# SmartClock.net
KiCad netlist of a schematic drawn in EAGLE
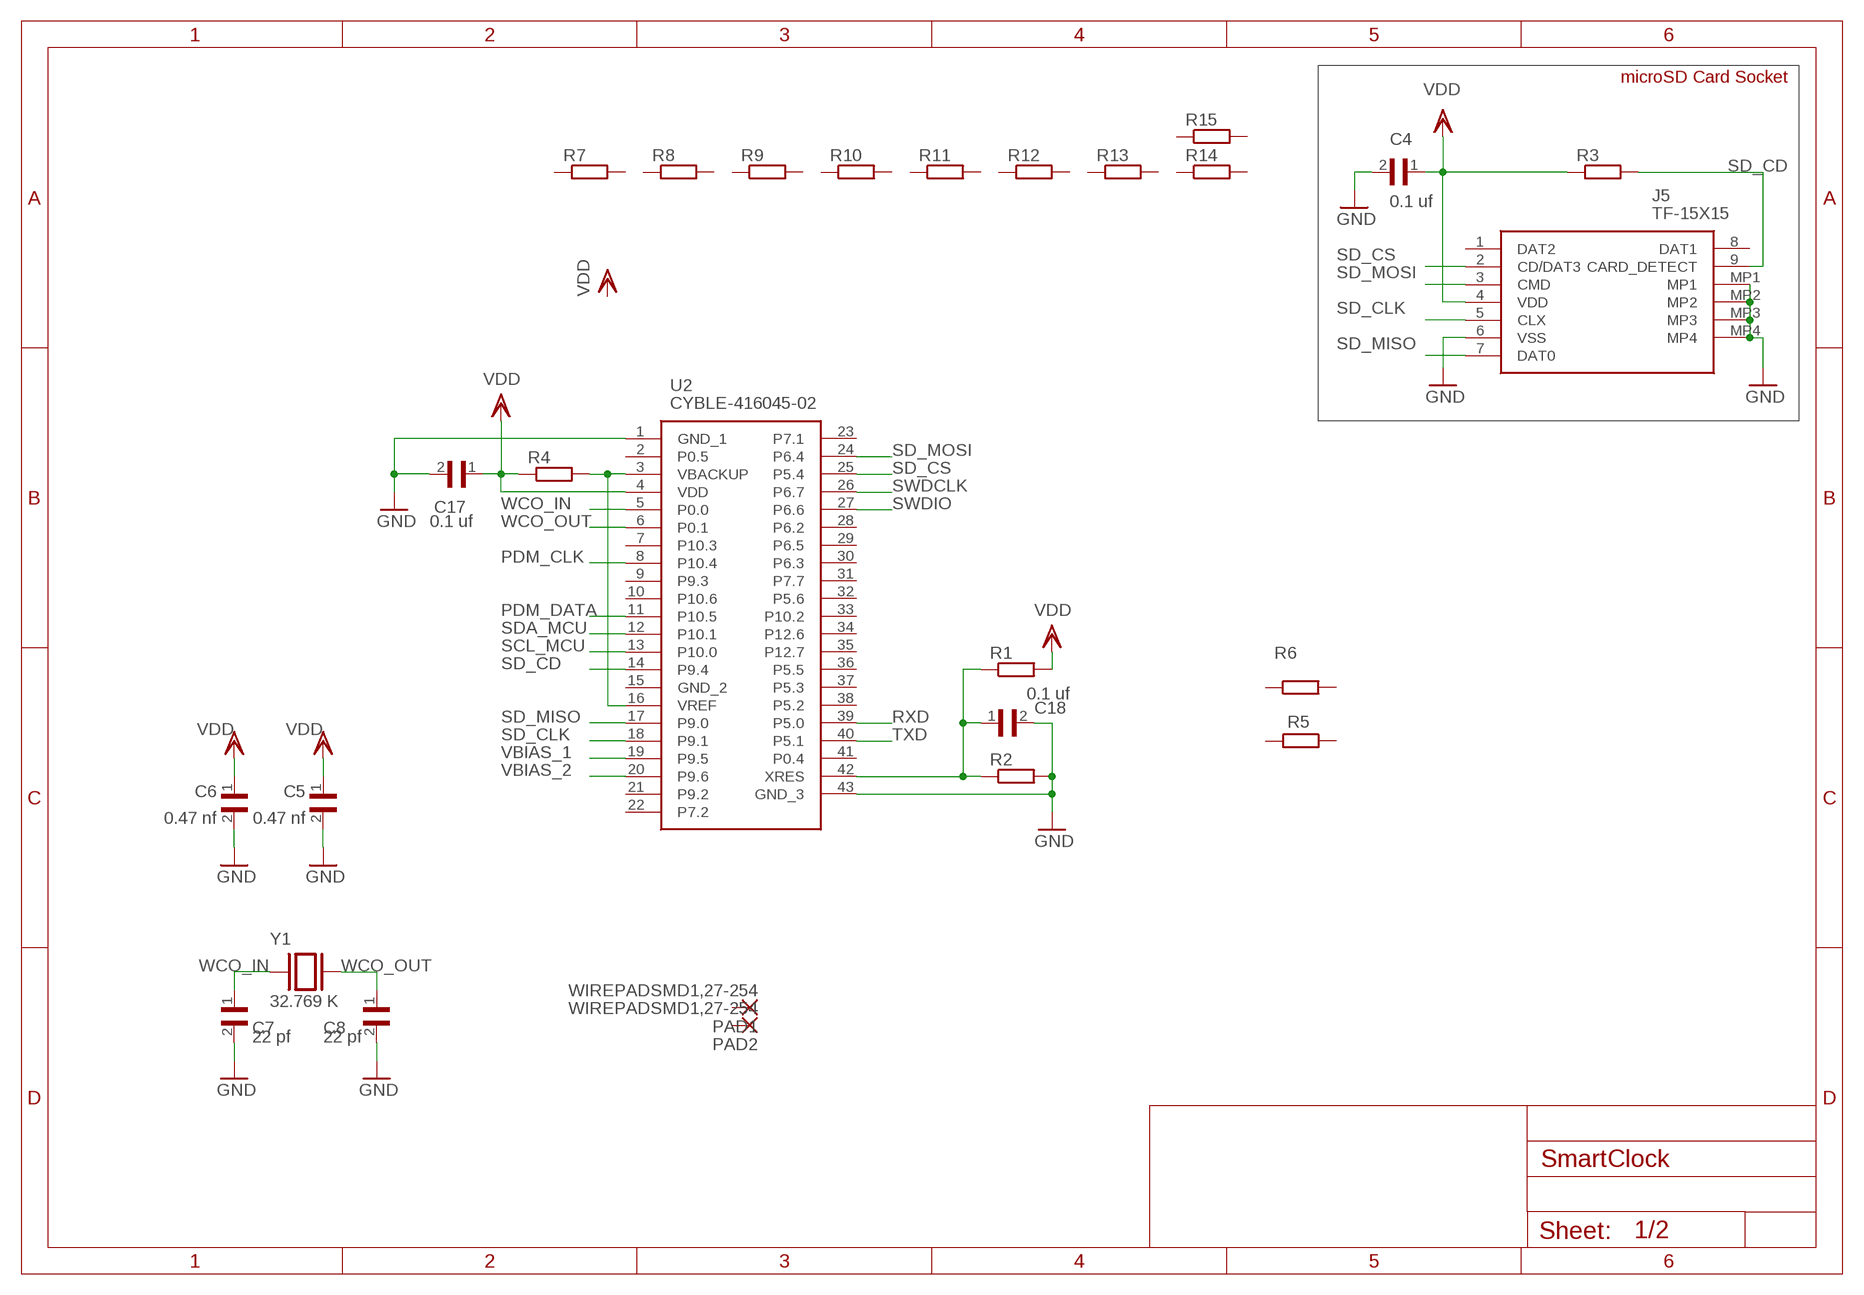
[diagram p0: schematic, sheet 1]
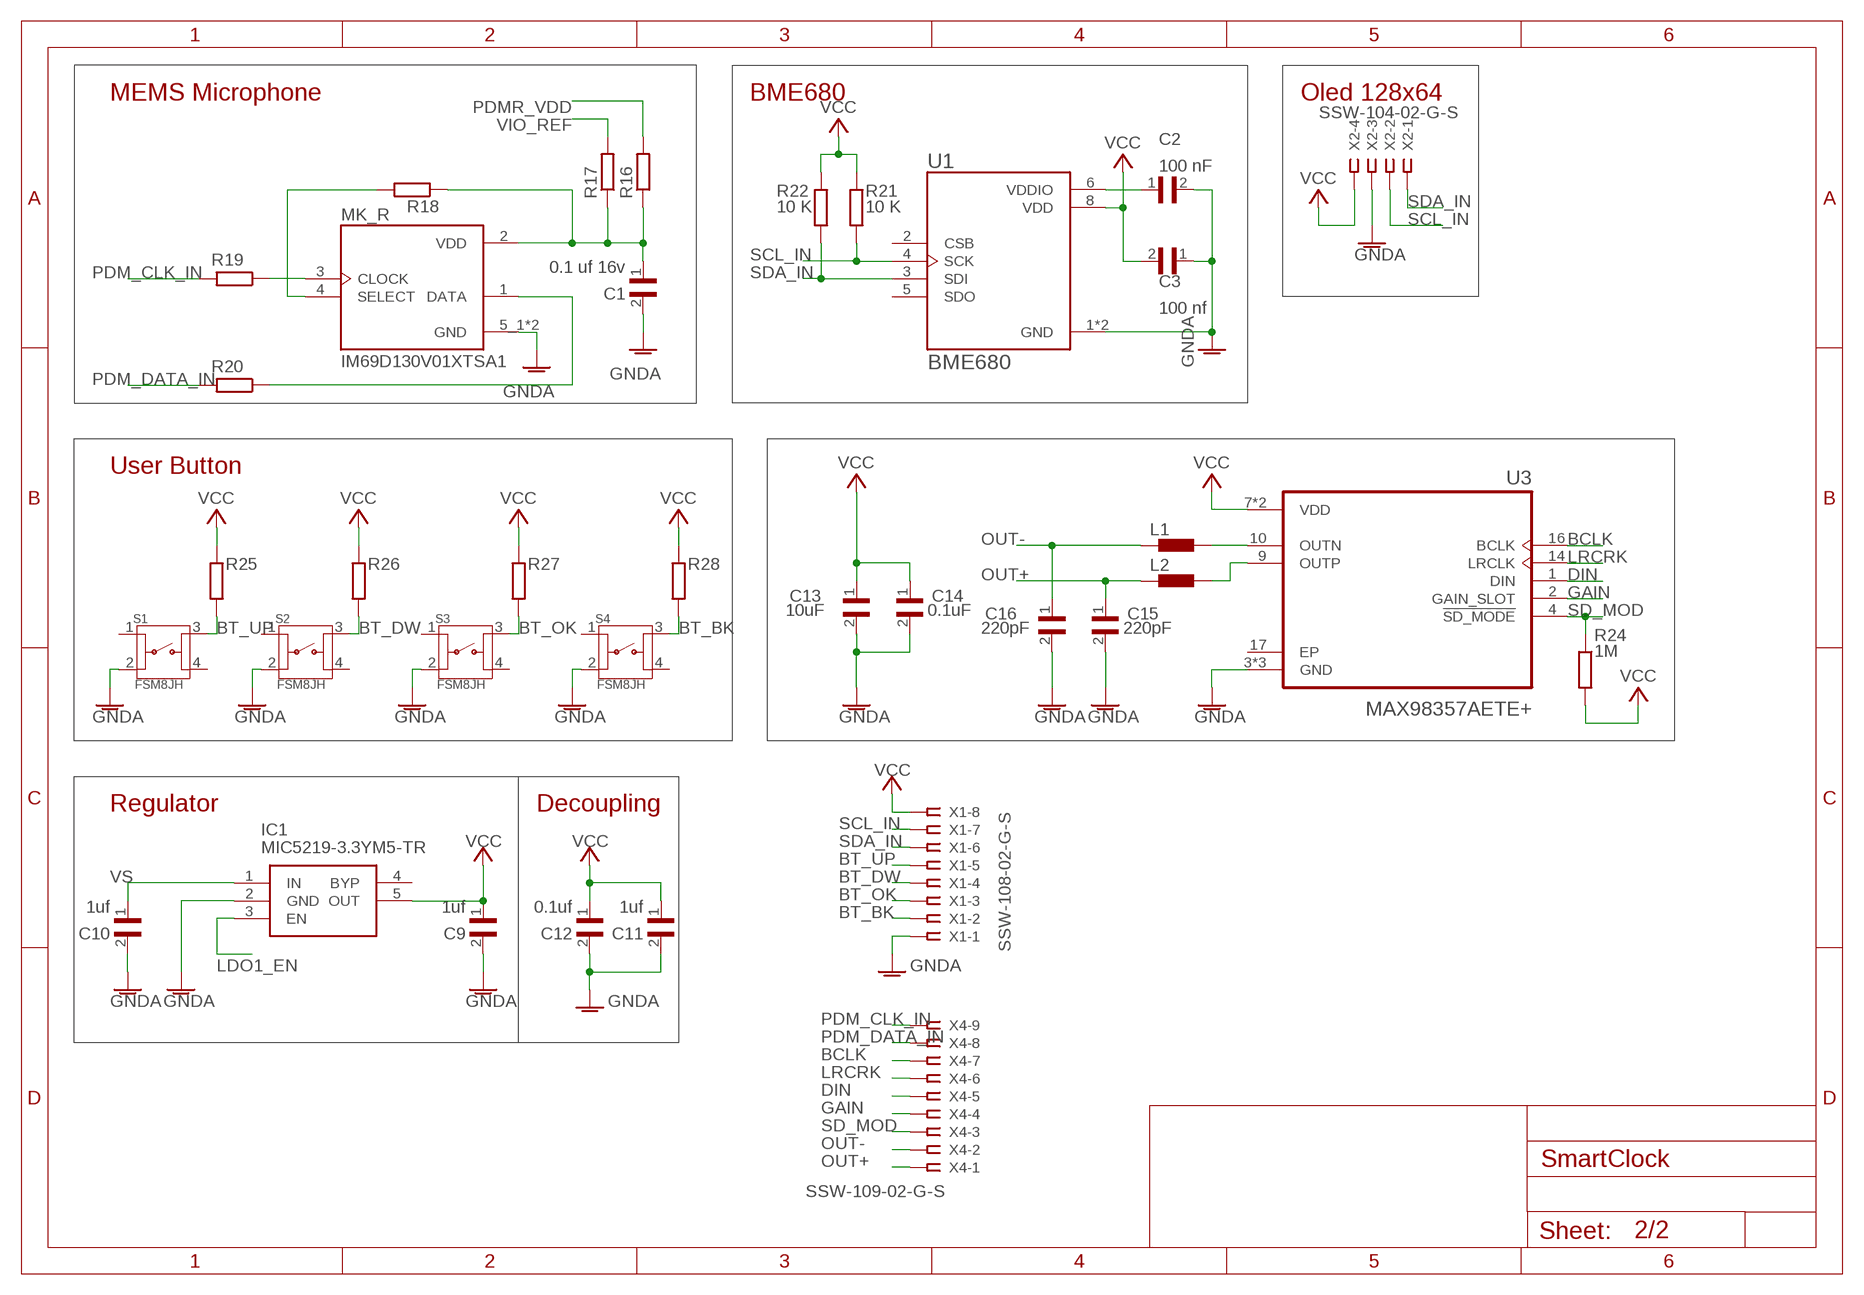
[diagram p1: schematic, sheet 2]

(export (version "E")
  (design (tool "Eeschema 10.0.6"))
  (components
    (comp (ref "C4")
      (value "0.1 uf")
      (footprint "eagle-import:CAPC1608X90")
      (fields (field (name "MF") "KEMET") (field (name "MP") "C0603C103K5RAC"))
      (libsource (lib "eagle-import") (part "C0603C103K5RAC"))
    )
    (comp (ref "C5")
      (value "0.47 nf")
      (footprint "eagle-import:CAPC1608X90")
      (fields (field (name "MF") "KEMET") (field (name "MP") "C0603C103K5RAC"))
      (libsource (lib "eagle-import") (part "C0603C103K5RAC"))
    )
    (comp (ref "C6")
      (value "0.47 nf")
      (footprint "eagle-import:CAPC1608X90")
      (fields (field (name "MF") "KEMET") (field (name "MP") "C0603C103K5RAC"))
      (libsource (lib "eagle-import") (part "C0603C103K5RAC"))
    )
    (comp (ref "C7")
      (value "22 pf")
      (footprint "eagle-import:CAPC1608X90")
      (fields (field (name "MF") "KEMET") (field (name "MP") "C0603C103K5RAC"))
      (libsource (lib "eagle-import") (part "C0603C103K5RAC"))
    )
    (comp (ref "C8")
      (value "22 pf")
      (footprint "eagle-import:CAPC1608X90")
      (fields (field (name "MF") "KEMET") (field (name "MP") "C0603C103K5RAC"))
      (libsource (lib "eagle-import") (part "C0603C103K5RAC"))
    )
    (comp (ref "C17")
      (value "0.1 uf")
      (footprint "eagle-import:CAPC1608X90")
      (fields (field (name "MF") "KEMET") (field (name "MP") "C0603C103K5RAC"))
      (libsource (lib "eagle-import") (part "C0603C103K5RAC"))
    )
    (comp (ref "C18")
      (value "0.1 uf")
      (footprint "eagle-import:CAPC1608X90")
      (fields (field (name "MF") "KEMET") (field (name "MP") "C0603C103K5RAC"))
      (libsource (lib "eagle-import") (part "C0603C103K5RAC"))
    )
    (comp (ref "J5")
      (value "TF-15X15")
      (footprint "eagle-import:TF15X15")
      (libsource (lib "eagle-import") (part "TF-15X15"))
    )
    (comp (ref "PAD1")
      (value "WIREPADSMD1,27-254")
      (footprint "eagle-import:SMD1,27-2,54")
      (libsource (lib "eagle-import") (part "WIREPADSMD1,27-254"))
    )
    (comp (ref "PAD2")
      (value "WIREPADSMD1,27-254")
      (footprint "eagle-import:SMD1,27-2,54")
      (libsource (lib "eagle-import") (part "WIREPADSMD1,27-254"))
    )
    (comp (ref "R1")
      (value "R-EU_R0603")
      (footprint "eagle-import:R0603")
      (libsource (lib "eagle-import") (part "R-EU_R0603"))
    )
    (comp (ref "R2")
      (value "R-EU_R0603")
      (footprint "eagle-import:R0603")
      (libsource (lib "eagle-import") (part "R-EU_R0603"))
    )
    (comp (ref "R3")
      (value "R-EU_R0603")
      (footprint "eagle-import:R0603")
      (libsource (lib "eagle-import") (part "R-EU_R0603"))
    )
    (comp (ref "R4")
      (value "R-EU_R0603")
      (footprint "eagle-import:R0603")
      (libsource (lib "eagle-import") (part "R-EU_R0603"))
    )
    (comp (ref "R5")
      (value "R-EU_R0603")
      (footprint "eagle-import:R0603")
      (libsource (lib "eagle-import") (part "R-EU_R0603"))
    )
    (comp (ref "R6")
      (value "R-EU_R0603")
      (footprint "eagle-import:R0603")
      (libsource (lib "eagle-import") (part "R-EU_R0603"))
    )
    (comp (ref "R7")
      (value "R-EU_R0603")
      (footprint "eagle-import:R0603")
      (libsource (lib "eagle-import") (part "R-EU_R0603"))
    )
    (comp (ref "R8")
      (value "R-EU_R0603")
      (footprint "eagle-import:R0603")
      (libsource (lib "eagle-import") (part "R-EU_R0603"))
    )
    (comp (ref "R9")
      (value "R-EU_R0603")
      (footprint "eagle-import:R0603")
      (libsource (lib "eagle-import") (part "R-EU_R0603"))
    )
    (comp (ref "R10")
      (value "R-EU_R0603")
      (footprint "eagle-import:R0603")
      (libsource (lib "eagle-import") (part "R-EU_R0603"))
    )
    (comp (ref "R11")
      (value "R-EU_R0603")
      (footprint "eagle-import:R0603")
      (libsource (lib "eagle-import") (part "R-EU_R0603"))
    )
    (comp (ref "R12")
      (value "R-EU_R0603")
      (footprint "eagle-import:R0603")
      (libsource (lib "eagle-import") (part "R-EU_R0603"))
    )
    (comp (ref "R13")
      (value "R-EU_R0603")
      (footprint "eagle-import:R0603")
      (libsource (lib "eagle-import") (part "R-EU_R0603"))
    )
    (comp (ref "R14")
      (value "R-EU_R0603")
      (footprint "eagle-import:R0603")
      (libsource (lib "eagle-import") (part "R-EU_R0603"))
    )
    (comp (ref "R15")
      (value "R-EU_R0603")
      (footprint "eagle-import:R0603")
      (libsource (lib "eagle-import") (part "R-EU_R0603"))
    )
    (comp (ref "U2")
      (value "CYBLE-416045-02")
      (footprint "eagle-import:CYBLE41604502")
      (fields (field (name "MOUSER_PART_NUMBER") "727-CYBLE-416045-02"))
      (libsource (lib "eagle-import") (part "CYBLE-416045-02"))
    )
    (comp (ref "Y1")
      (value "32.769 K")
      (footprint "eagle-import:XTAL_MS3V-T1R")
      (fields (field (name "MF") "Micro Crystal") (field (name "MP") "MS3V-T1R"))
      (libsource (lib "eagle-import") (part "MS3V-T1R"))
    )
    (comp (ref "C1")
      (value "0.1 uf 16v")
      (footprint "eagle-import:CAPC1608X90")
      (fields (field (name "MF") "KEMET") (field (name "MP") "C0603C103K5RAC"))
      (libsource (lib "eagle-import") (part "C0603C103K5RAC"))
    )
    (comp (ref "C2")
      (value "100 nF")
      (footprint "eagle-import:CAPC1608X90")
      (fields (field (name "MF") "KEMET") (field (name "MP") "C0603C103K5RAC"))
      (libsource (lib "eagle-import") (part "C0603C103K5RAC"))
    )
    (comp (ref "C3")
      (value "100 nf")
      (footprint "eagle-import:CAPC1608X90")
      (fields (field (name "MF") "KEMET") (field (name "MP") "C0603C103K5RAC"))
      (libsource (lib "eagle-import") (part "C0603C103K5RAC"))
    )
    (comp (ref "C9")
      (value "1uf")
      (footprint "eagle-import:CAPC1608X90")
      (fields (field (name "MF") "KEMET") (field (name "MP") "C0603C103K5RAC"))
      (libsource (lib "eagle-import") (part "C0603C103K5RAC"))
    )
    (comp (ref "C10")
      (value "1uf")
      (footprint "eagle-import:CAPC1608X90")
      (fields (field (name "MF") "KEMET") (field (name "MP") "C0603C103K5RAC"))
      (libsource (lib "eagle-import") (part "C0603C103K5RAC"))
    )
    (comp (ref "C11")
      (value "1uf")
      (footprint "eagle-import:CAPC1608X90")
      (fields (field (name "MF") "KEMET") (field (name "MP") "C0603C103K5RAC"))
      (libsource (lib "eagle-import") (part "C0603C103K5RAC"))
    )
    (comp (ref "C12")
      (value "0.1uf")
      (footprint "eagle-import:CAPC1608X90")
      (fields (field (name "MF") "KEMET") (field (name "MP") "C0603C103K5RAC"))
      (libsource (lib "eagle-import") (part "C0603C103K5RAC"))
    )
    (comp (ref "C13")
      (value "10uF")
      (footprint "eagle-import:CAPC1608X90")
      (fields (field (name "MF") "KEMET") (field (name "MP") "C0603C103K5RAC"))
      (libsource (lib "eagle-import") (part "C0603C103K5RAC"))
    )
    (comp (ref "C14")
      (value "0.1uF")
      (footprint "eagle-import:CAPC1608X90")
      (fields (field (name "MF") "KEMET") (field (name "MP") "C0603C103K5RAC"))
      (libsource (lib "eagle-import") (part "C0603C103K5RAC"))
    )
    (comp (ref "C15")
      (value "220pF")
      (footprint "eagle-import:CAPC1608X90")
      (fields (field (name "MF") "KEMET") (field (name "MP") "C0603C103K5RAC"))
      (libsource (lib "eagle-import") (part "C0603C103K5RAC"))
    )
    (comp (ref "C16")
      (value "220pF")
      (footprint "eagle-import:CAPC1608X90")
      (fields (field (name "MF") "KEMET") (field (name "MP") "C0603C103K5RAC"))
      (libsource (lib "eagle-import") (part "C0603C103K5RAC"))
    )
    (comp (ref "IC1")
      (value "MIC5219-3.3YM5-TR")
      (footprint "eagle-import:SOT95P280X145-5N")
      (fields (field (name "MOUSER_PART_NUMBER") "998-MIC5219-3.3YM5TR"))
      (libsource (lib "eagle-import") (part "MIC5219-3.3YM5-TR"))
    )
    (comp (ref "L1")
      (value "BLM15HB121SN1")
      (footprint "eagle-import:0402")
      (libsource (lib "eagle-import") (part "BLM15HB121SN1"))
    )
    (comp (ref "L2")
      (value "BLM15HB121SN1")
      (footprint "eagle-import:0402")
      (libsource (lib "eagle-import") (part "BLM15HB121SN1"))
    )
    (comp (ref "MK_R")
      (value "IM69D130V01XTSA1")
      (footprint "eagle-import:MIC_IM69D130V01XTSA1")
      (fields (field (name "MF") "Infineon Technologies"))
      (libsource (lib "eagle-import") (part "IM69D130V01XTSA1"))
    )
    (comp (ref "R16")
      (value "R-EU_R0603")
      (footprint "eagle-import:R0603")
      (libsource (lib "eagle-import") (part "R-EU_R0603"))
    )
    (comp (ref "R17")
      (value "R-EU_R0603")
      (footprint "eagle-import:R0603")
      (libsource (lib "eagle-import") (part "R-EU_R0603"))
    )
    (comp (ref "R18")
      (value "R-EU_R0603")
      (footprint "eagle-import:R0603")
      (libsource (lib "eagle-import") (part "R-EU_R0603"))
    )
    (comp (ref "R19")
      (value "R-EU_R0603")
      (footprint "eagle-import:R0603")
      (libsource (lib "eagle-import") (part "R-EU_R0603"))
    )
    (comp (ref "R20")
      (value "R-EU_R0603")
      (footprint "eagle-import:R0603")
      (libsource (lib "eagle-import") (part "R-EU_R0603"))
    )
    (comp (ref "R21")
      (value "10 K")
      (footprint "eagle-import:R0603")
      (libsource (lib "eagle-import") (part "R-EU_R0603"))
    )
    (comp (ref "R22")
      (value "10 K")
      (footprint "eagle-import:R0603")
      (libsource (lib "eagle-import") (part "R-EU_R0603"))
    )
    (comp (ref "R24")
      (value "1M")
      (footprint "eagle-import:R0603")
      (libsource (lib "eagle-import") (part "R-EU_R0603"))
    )
    (comp (ref "R25")
      (value "R-EU_R0603")
      (footprint "eagle-import:R0603")
      (libsource (lib "eagle-import") (part "R-EU_R0603"))
    )
    (comp (ref "R26")
      (value "R-EU_R0603")
      (footprint "eagle-import:R0603")
      (libsource (lib "eagle-import") (part "R-EU_R0603"))
    )
    (comp (ref "R27")
      (value "R-EU_R0603")
      (footprint "eagle-import:R0603")
      (libsource (lib "eagle-import") (part "R-EU_R0603"))
    )
    (comp (ref "R28")
      (value "R-EU_R0603")
      (footprint "eagle-import:R0603")
      (libsource (lib "eagle-import") (part "R-EU_R0603"))
    )
    (comp (ref "S1")
      (value "FSM8JH")
      (footprint "eagle-import:SW_FSM8JH")
      (fields (field (name "MF") "TE Connectivity"))
      (libsource (lib "eagle-import") (part "FSM8JH"))
    )
    (comp (ref "S2")
      (value "FSM8JH")
      (footprint "eagle-import:SW_FSM8JH")
      (fields (field (name "MF") "TE Connectivity"))
      (libsource (lib "eagle-import") (part "FSM8JH"))
    )
    (comp (ref "S3")
      (value "FSM8JH")
      (footprint "eagle-import:SW_FSM8JH")
      (fields (field (name "MF") "TE Connectivity"))
      (libsource (lib "eagle-import") (part "FSM8JH"))
    )
    (comp (ref "S4")
      (value "FSM8JH")
      (footprint "eagle-import:SW_FSM8JH")
      (fields (field (name "MF") "TE Connectivity"))
      (libsource (lib "eagle-import") (part "FSM8JH"))
    )
    (comp (ref "U1")
      (value "BME680")
      (footprint "eagle-import:PSON80P300X300X100-8N")
      (fields (field (name "MF") "Bosch Sensortec"))
      (libsource (lib "eagle-import") (part "BME680"))
    )
    (comp (ref "U3")
      (value "MAX98357AETE+")
      (footprint "eagle-import:QFN50P300X300X80-17N")
      (fields (field (name "MF") "Analog Devices"))
      (libsource (lib "eagle-import") (part "MAX98357AETE+"))
    )
    (comp (ref "X1")
      (value "SSW-108-02-G-S")
      (footprint "eagle-import:SSW-108-02-G-S")
      (fields (field (name "MF") "Samtec Inc."))
      (libsource (lib "eagle-import") (part "SSW-108-02-G-S"))
    )
    (comp (ref "X2")
      (value "SSW-104-02-G-S")
      (footprint "eagle-import:SSW-104-02-G-S")
      (fields (field (name "MF") "Samtec Inc."))
      (libsource (lib "eagle-import") (part "SSW-104-02-G-S"))
    )
    (comp (ref "X4")
      (value "SSW-109-02-G-S")
      (footprint "eagle-import:SSW-109-02-G-S")
      (fields (field (name "MF") "Samtec Inc."))
      (libsource (lib "eagle-import") (part "SSW-109-02-G-S"))
    )
  )
  (nets
    (net (code "1") (name "BCLK") (class "Default")
      (node (ref "U3") (pin "16") (pinfunction "BCLK_16") (pintype "input"))
      (node (ref "X4") (pin "7") (pinfunction "1_7") (pintype "passive"))
    )
    (net (code "2") (name "BT_BK") (class "Default")
      (node (ref "R28") (pin "2") (pinfunction "2_2") (pintype "passive"))
      (node (ref "S4") (pin "3") (pinfunction "3_3") (pintype "passive"))
      (node (ref "X1") (pin "2") (pinfunction "1_2") (pintype "passive"))
    )
    (net (code "3") (name "BT_DW") (class "Default")
      (node (ref "R26") (pin "2") (pinfunction "2_2") (pintype "passive"))
      (node (ref "S2") (pin "3") (pinfunction "3_3") (pintype "passive"))
      (node (ref "X1") (pin "4") (pinfunction "1_4") (pintype "passive"))
    )
    (net (code "4") (name "BT_OK") (class "Default")
      (node (ref "R27") (pin "2") (pinfunction "2_2") (pintype "passive"))
      (node (ref "S3") (pin "3") (pinfunction "3_3") (pintype "passive"))
      (node (ref "X1") (pin "3") (pinfunction "1_3") (pintype "passive"))
    )
    (net (code "5") (name "BT_UP") (class "Default")
      (node (ref "R25") (pin "2") (pinfunction "2_2") (pintype "passive"))
      (node (ref "S1") (pin "3") (pinfunction "3_3") (pintype "passive"))
      (node (ref "X1") (pin "5") (pinfunction "1_5") (pintype "passive"))
    )
    (net (code "6") (name "DIN") (class "Default")
      (node (ref "U3") (pin "1") (pinfunction "DIN_1") (pintype "input"))
      (node (ref "X4") (pin "5") (pinfunction "1_5") (pintype "passive"))
    )
    (net (code "7") (name "EP") (class "Default")
      (node (ref "U3") (pin "17") (pinfunction "EP_17") (pintype "power_in"))
    )
    (net (code "8") (name "GAIN") (class "Default")
      (node (ref "U3") (pin "2") (pinfunction "GAIN_SLOT_2") (pintype "input"))
      (node (ref "X4") (pin "4") (pinfunction "1_4") (pintype "passive"))
    )
    (net (code "9") (name "GND") (class "Default")
      (node (ref "C17") (pin "2") (pinfunction "2_2") (pintype "passive"))
      (node (ref "C18") (pin "2") (pinfunction "2_2") (pintype "passive"))
      (node (ref "C4") (pin "2") (pinfunction "2_2") (pintype "passive"))
      (node (ref "C5") (pin "2") (pinfunction "2_2") (pintype "passive"))
      (node (ref "C6") (pin "2") (pinfunction "2_2") (pintype "passive"))
      (node (ref "C7") (pin "2") (pinfunction "2_2") (pintype "passive"))
      (node (ref "C8") (pin "2") (pinfunction "2_2") (pintype "passive"))
      (node (ref "J5") (pin "6") (pinfunction "VSS_6") (pintype "bidirectional"))
      (node (ref "J5") (pin "MP1") (pinfunction "MP1_MP1") (pintype "bidirectional"))
      (node (ref "J5") (pin "MP2") (pinfunction "MP2_MP2") (pintype "bidirectional"))
      (node (ref "J5") (pin "MP3") (pinfunction "MP3_MP3") (pintype "bidirectional"))
      (node (ref "J5") (pin "MP4") (pinfunction "MP4_MP4") (pintype "bidirectional"))
      (node (ref "R2") (pin "2") (pinfunction "2_2") (pintype "passive"))
      (node (ref "U2") (pin "1") (pinfunction "GND_1_1") (pintype "bidirectional"))
      (node (ref "U2") (pin "43") (pinfunction "GND_3_43") (pintype "bidirectional"))
    )
    (net (code "10") (name "GNDA") (class "Default")
      (node (ref "C1") (pin "2") (pinfunction "2_2") (pintype "passive"))
      (node (ref "C10") (pin "2") (pinfunction "2_2") (pintype "passive"))
      (node (ref "C11") (pin "2") (pinfunction "2_2") (pintype "passive"))
      (node (ref "C12") (pin "2") (pinfunction "2_2") (pintype "passive"))
      (node (ref "C13") (pin "2") (pinfunction "2_2") (pintype "passive"))
      (node (ref "C14") (pin "2") (pinfunction "2_2") (pintype "passive"))
      (node (ref "C15") (pin "2") (pinfunction "2_2") (pintype "passive"))
      (node (ref "C16") (pin "2") (pinfunction "2_2") (pintype "passive"))
      (node (ref "C2") (pin "2") (pinfunction "2_2") (pintype "passive"))
      (node (ref "C3") (pin "1") (pinfunction "1_1") (pintype "passive"))
      (node (ref "C9") (pin "2") (pinfunction "2_2") (pintype "passive"))
      (node (ref "IC1") (pin "2") (pinfunction "GND_2") (pintype "bidirectional"))
      (node (ref "MK_R") (pin "5_1") (pinfunction "GND_5_1") (pintype "power_in"))
      (node (ref "MK_R") (pin "5_2") (pinfunction "GND_5_2") (pintype "power_in"))
      (node (ref "S1") (pin "2") (pinfunction "2_2") (pintype "passive"))
      (node (ref "S2") (pin "2") (pinfunction "2_2") (pintype "passive"))
      (node (ref "S3") (pin "2") (pinfunction "2_2") (pintype "passive"))
      (node (ref "S4") (pin "2") (pinfunction "2_2") (pintype "passive"))
      (node (ref "U1") (pin "1") (pinfunction "GND_1") (pintype "power_in"))
      (node (ref "U1") (pin "7") (pinfunction "GND_7") (pintype "power_in"))
      (node (ref "U3") (pin "11") (pinfunction "GND_11") (pintype "power_in"))
      (node (ref "U3") (pin "15") (pinfunction "GND_15") (pintype "power_in"))
      (node (ref "U3") (pin "3") (pinfunction "GND_3") (pintype "power_in"))
      (node (ref "X1") (pin "1") (pinfunction "1_1") (pintype "passive"))
      (node (ref "X2") (pin "3") (pinfunction "1_3") (pintype "passive"))
    )
    (net (code "11") (name "LDO1_EN") (class "Default")
      (node (ref "IC1") (pin "3") (pinfunction "EN_3") (pintype "bidirectional"))
    )
    (net (code "12") (name "LRCRK") (class "Default")
      (node (ref "U3") (pin "14") (pinfunction "LRCLK_14") (pintype "input"))
      (node (ref "X4") (pin "6") (pinfunction "1_6") (pintype "passive"))
    )
    (net (code "13") (name "Net-(MK_R-CLOCK)") (class "Default")
      (node (ref "MK_R") (pin "3") (pinfunction "CLOCK_3") (pintype "input"))
      (node (ref "R19") (pin "1") (pinfunction "1_1") (pintype "passive"))
    )
    (net (code "14") (name "Net-(MK_R-DATA)") (class "Default")
      (node (ref "MK_R") (pin "1") (pinfunction "DATA_1") (pintype "output"))
      (node (ref "R20") (pin "1") (pinfunction "1_1") (pintype "passive"))
    )
    (net (code "15") (name "Net-(MK_R-SELECT)") (class "Default")
      (node (ref "MK_R") (pin "4") (pinfunction "SELECT_4") (pintype "input"))
      (node (ref "R18") (pin "2") (pinfunction "2_2") (pintype "passive"))
    )
    (net (code "16") (name "Net-(MK_R-VDD)") (class "Default")
      (node (ref "C1") (pin "1") (pinfunction "1_1") (pintype "passive"))
      (node (ref "MK_R") (pin "2") (pinfunction "VDD_2") (pintype "power_in"))
      (node (ref "R16") (pin "1") (pinfunction "1_1") (pintype "passive"))
      (node (ref "R17") (pin "1") (pinfunction "1_1") (pintype "passive"))
      (node (ref "R18") (pin "1") (pinfunction "1_1") (pintype "passive"))
    )
    (net (code "17") (name "Net-(U1-VDDIO)") (class "Default")
      (node (ref "C2") (pin "1") (pinfunction "1_1") (pintype "passive"))
      (node (ref "U1") (pin "6") (pinfunction "VDDIO_6") (pintype "power_in"))
    )
    (net (code "18") (name "Net-(U2-VBACKUP)") (class "Default")
      (node (ref "R4") (pin "2") (pinfunction "2_2") (pintype "passive"))
      (node (ref "U2") (pin "16") (pinfunction "VREF_16") (pintype "bidirectional"))
      (node (ref "U2") (pin "3") (pinfunction "VBACKUP_3") (pintype "bidirectional"))
    )
    (net (code "19") (name "Net-(U2-XRES)") (class "Default")
      (node (ref "C18") (pin "1") (pinfunction "1_1") (pintype "passive"))
      (node (ref "R1") (pin "1") (pinfunction "1_1") (pintype "passive"))
      (node (ref "R2") (pin "1") (pinfunction "1_1") (pintype "passive"))
      (node (ref "U2") (pin "42") (pinfunction "XRES_42") (pintype "bidirectional"))
    )
    (net (code "20") (name "Net-(U3-OUTN)") (class "Default")
      (node (ref "L1") (pin "2") (pinfunction "2_2") (pintype "passive"))
      (node (ref "U3") (pin "10") (pinfunction "OUTN_10") (pintype "output"))
    )
    (net (code "21") (name "Net-(U3-OUTP)") (class "Default")
      (node (ref "L2") (pin "2") (pinfunction "2_2") (pintype "passive"))
      (node (ref "U3") (pin "9") (pinfunction "OUTP_9") (pintype "output"))
    )
    (net (code "22") (name "OUT+") (class "Default")
      (node (ref "C15") (pin "1") (pinfunction "1_1") (pintype "passive"))
      (node (ref "L2") (pin "1") (pinfunction "1_1") (pintype "passive"))
      (node (ref "X4") (pin "1") (pinfunction "1_1") (pintype "passive"))
    )
    (net (code "23") (name "OUT-") (class "Default")
      (node (ref "C16") (pin "1") (pinfunction "1_1") (pintype "passive"))
      (node (ref "L1") (pin "1") (pinfunction "1_1") (pintype "passive"))
      (node (ref "X4") (pin "2") (pinfunction "1_2") (pintype "passive"))
    )
    (net (code "24") (name "PDMR_VDD") (class "Default")
      (node (ref "R16") (pin "2") (pinfunction "2_2") (pintype "passive"))
    )
    (net (code "25") (name "PDM_CLK") (class "Default")
      (node (ref "U2") (pin "8") (pinfunction "P10.4_8") (pintype "bidirectional"))
    )
    (net (code "26") (name "PDM_CLK_IN") (class "Default")
      (node (ref "R19") (pin "2") (pinfunction "2_2") (pintype "passive"))
      (node (ref "X4") (pin "9") (pinfunction "1_9") (pintype "passive"))
    )
    (net (code "27") (name "PDM_DATA") (class "Default")
      (node (ref "U2") (pin "11") (pinfunction "P10.5_11") (pintype "bidirectional"))
    )
    (net (code "28") (name "PDM_DATA_IN") (class "Default")
      (node (ref "R20") (pin "2") (pinfunction "2_2") (pintype "passive"))
      (node (ref "X4") (pin "8") (pinfunction "1_8") (pintype "passive"))
    )
    (net (code "29") (name "RXD") (class "Default")
      (node (ref "U2") (pin "39") (pinfunction "P5.0_39") (pintype "bidirectional"))
    )
    (net (code "30") (name "SCL_IN") (class "Default")
      (node (ref "R21") (pin "2") (pinfunction "2_2") (pintype "passive"))
      (node (ref "U1") (pin "4") (pinfunction "SCK_4") (pintype "input"))
      (node (ref "X1") (pin "7") (pinfunction "1_7") (pintype "passive"))
      (node (ref "X2") (pin "2") (pinfunction "1_2") (pintype "passive"))
    )
    (net (code "31") (name "SCL_MCU") (class "Default")
      (node (ref "U2") (pin "13") (pinfunction "P10.0_13") (pintype "bidirectional"))
    )
    (net (code "32") (name "SDA_IN") (class "Default")
      (node (ref "R22") (pin "2") (pinfunction "2_2") (pintype "passive"))
      (node (ref "U1") (pin "3") (pinfunction "SDI_3") (pintype "bidirectional"))
      (node (ref "X1") (pin "6") (pinfunction "1_6") (pintype "passive"))
      (node (ref "X2") (pin "1") (pinfunction "1_1") (pintype "passive"))
    )
    (net (code "33") (name "SDA_MCU") (class "Default")
      (node (ref "U2") (pin "12") (pinfunction "P10.1_12") (pintype "bidirectional"))
    )
    (net (code "34") (name "SD_CD") (class "Default")
      (node (ref "J5") (pin "9") (pinfunction "CARD_DETECT_9") (pintype "bidirectional"))
      (node (ref "R3") (pin "2") (pinfunction "2_2") (pintype "passive"))
      (node (ref "U2") (pin "14") (pinfunction "P9.4_14") (pintype "bidirectional"))
    )
    (net (code "35") (name "SD_CLK") (class "Default")
      (node (ref "J5") (pin "5") (pinfunction "CLX_5") (pintype "bidirectional"))
      (node (ref "U2") (pin "18") (pinfunction "P9.1_18") (pintype "bidirectional"))
    )
    (net (code "36") (name "SD_CS") (class "Default")
      (node (ref "J5") (pin "2") (pinfunction "CD/DAT3_2") (pintype "bidirectional"))
      (node (ref "U2") (pin "25") (pinfunction "P5.4_25") (pintype "bidirectional"))
    )
    (net (code "37") (name "SD_MISO") (class "Default")
      (node (ref "J5") (pin "7") (pinfunction "DAT0_7") (pintype "bidirectional"))
      (node (ref "U2") (pin "17") (pinfunction "P9.0_17") (pintype "bidirectional"))
    )
    (net (code "38") (name "SD_MOD") (class "Default")
      (node (ref "R24") (pin "1") (pinfunction "1_1") (pintype "passive"))
      (node (ref "U3") (pin "4") (pinfunction "~{SD_MODE}_4") (pintype "input"))
      (node (ref "X4") (pin "3") (pinfunction "1_3") (pintype "passive"))
    )
    (net (code "39") (name "SD_MOSI") (class "Default")
      (node (ref "J5") (pin "3") (pinfunction "CMD_3") (pintype "bidirectional"))
      (node (ref "U2") (pin "24") (pinfunction "P6.4_24") (pintype "bidirectional"))
    )
    (net (code "40") (name "SWDCLK") (class "Default")
      (node (ref "U2") (pin "26") (pinfunction "P6.7_26") (pintype "bidirectional"))
    )
    (net (code "41") (name "SWDIO") (class "Default")
      (node (ref "U2") (pin "27") (pinfunction "P6.6_27") (pintype "bidirectional"))
    )
    (net (code "42") (name "TXD") (class "Default")
      (node (ref "U2") (pin "40") (pinfunction "P5.1_40") (pintype "bidirectional"))
    )
    (net (code "43") (name "VBIAS_1") (class "Default")
      (node (ref "U2") (pin "19") (pinfunction "P9.5_19") (pintype "bidirectional"))
    )
    (net (code "44") (name "VBIAS_2") (class "Default")
      (node (ref "U2") (pin "20") (pinfunction "P9.6_20") (pintype "bidirectional"))
    )
    (net (code "45") (name "VCC") (class "Default")
      (node (ref "C11") (pin "1") (pinfunction "1_1") (pintype "passive"))
      (node (ref "C12") (pin "1") (pinfunction "1_1") (pintype "passive"))
      (node (ref "C13") (pin "1") (pinfunction "1_1") (pintype "passive"))
      (node (ref "C14") (pin "1") (pinfunction "1_1") (pintype "passive"))
      (node (ref "C3") (pin "2") (pinfunction "2_2") (pintype "passive"))
      (node (ref "C9") (pin "1") (pinfunction "1_1") (pintype "passive"))
      (node (ref "IC1") (pin "5") (pinfunction "OUT_5") (pintype "bidirectional"))
      (node (ref "R21") (pin "1") (pinfunction "1_1") (pintype "passive"))
      (node (ref "R22") (pin "1") (pinfunction "1_1") (pintype "passive"))
      (node (ref "R24") (pin "2") (pinfunction "2_2") (pintype "passive"))
      (node (ref "R25") (pin "1") (pinfunction "1_1") (pintype "passive"))
      (node (ref "R26") (pin "1") (pinfunction "1_1") (pintype "passive"))
      (node (ref "R27") (pin "1") (pinfunction "1_1") (pintype "passive"))
      (node (ref "R28") (pin "1") (pinfunction "1_1") (pintype "passive"))
      (node (ref "U1") (pin "8") (pinfunction "VDD_8") (pintype "power_in"))
      (node (ref "U3") (pin "7") (pinfunction "VDD_7") (pintype "power_in"))
      (node (ref "U3") (pin "8") (pinfunction "VDD_8") (pintype "power_in"))
      (node (ref "X1") (pin "8") (pinfunction "1_8") (pintype "passive"))
      (node (ref "X2") (pin "4") (pinfunction "1_4") (pintype "passive"))
    )
    (net (code "46") (name "VDD") (class "Default")
      (node (ref "C17") (pin "1") (pinfunction "1_1") (pintype "passive"))
      (node (ref "C4") (pin "1") (pinfunction "1_1") (pintype "passive"))
      (node (ref "C5") (pin "1") (pinfunction "1_1") (pintype "passive"))
      (node (ref "C6") (pin "1") (pinfunction "1_1") (pintype "passive"))
      (node (ref "J5") (pin "4") (pinfunction "VDD_4") (pintype "bidirectional"))
      (node (ref "R1") (pin "2") (pinfunction "2_2") (pintype "passive"))
      (node (ref "R3") (pin "1") (pinfunction "1_1") (pintype "passive"))
      (node (ref "R4") (pin "1") (pinfunction "1_1") (pintype "passive"))
      (node (ref "U2") (pin "4") (pinfunction "VDD_4") (pintype "bidirectional"))
    )
    (net (code "47") (name "VIO_REF") (class "Default")
      (node (ref "R17") (pin "2") (pinfunction "2_2") (pintype "passive"))
    )
    (net (code "48") (name "VS") (class "Default")
      (node (ref "C10") (pin "1") (pinfunction "1_1") (pintype "passive"))
      (node (ref "IC1") (pin "1") (pinfunction "IN_1") (pintype "bidirectional"))
    )
    (net (code "49") (name "WCO_IN") (class "Default")
      (node (ref "C7") (pin "1") (pinfunction "1_1") (pintype "passive"))
      (node (ref "U2") (pin "5") (pinfunction "P0.0_5") (pintype "bidirectional"))
      (node (ref "Y1") (pin "1") (pinfunction "1_1") (pintype "passive"))
    )
    (net (code "50") (name "WCO_OUT") (class "Default")
      (node (ref "C8") (pin "1") (pinfunction "1_1") (pintype "passive"))
      (node (ref "U2") (pin "6") (pinfunction "P0.1_6") (pintype "bidirectional"))
      (node (ref "Y1") (pin "2") (pinfunction "2_2") (pintype "passive"))
    )
    (net (code "51") (name "unconnected-(IC1-BYP-Pad4)") (class "Default")
      (node (ref "IC1") (pin "4") (pinfunction "BYP_4") (pintype "bidirectional"))
    )
    (net (code "52") (name "unconnected-(J5-DAT1-Pad8)") (class "Default")
      (node (ref "J5") (pin "8") (pinfunction "DAT1_8") (pintype "bidirectional"))
    )
    (net (code "53") (name "unconnected-(J5-DAT2-Pad1)") (class "Default")
      (node (ref "J5") (pin "1") (pinfunction "DAT2_1") (pintype "bidirectional"))
    )
    (net (code "54") (name "unconnected-(PAD1-P-Pad1)") (class "Default")
      (node (ref "PAD1") (pin "1") (pinfunction "P_1") (pintype "passive"))
    )
    (net (code "55") (name "unconnected-(PAD2-P-Pad1)") (class "Default")
      (node (ref "PAD2") (pin "1") (pinfunction "P_1") (pintype "passive"))
    )
    (net (code "56") (name "unconnected-(R5-Pad1)") (class "Default")
      (node (ref "R5") (pin "1") (pinfunction "1_1") (pintype "passive"))
    )
    (net (code "57") (name "unconnected-(R5-Pad2)") (class "Default")
      (node (ref "R5") (pin "2") (pinfunction "2_2") (pintype "passive"))
    )
    (net (code "58") (name "unconnected-(R6-Pad1)") (class "Default")
      (node (ref "R6") (pin "1") (pinfunction "1_1") (pintype "passive"))
    )
    (net (code "59") (name "unconnected-(R6-Pad2)") (class "Default")
      (node (ref "R6") (pin "2") (pinfunction "2_2") (pintype "passive"))
    )
    (net (code "60") (name "unconnected-(R7-Pad1)") (class "Default")
      (node (ref "R7") (pin "1") (pinfunction "1_1") (pintype "passive"))
    )
    (net (code "61") (name "unconnected-(R7-Pad2)") (class "Default")
      (node (ref "R7") (pin "2") (pinfunction "2_2") (pintype "passive"))
    )
    (net (code "62") (name "unconnected-(R8-Pad1)") (class "Default")
      (node (ref "R8") (pin "1") (pinfunction "1_1") (pintype "passive"))
    )
    (net (code "63") (name "unconnected-(R8-Pad2)") (class "Default")
      (node (ref "R8") (pin "2") (pinfunction "2_2") (pintype "passive"))
    )
    (net (code "64") (name "unconnected-(R9-Pad1)") (class "Default")
      (node (ref "R9") (pin "1") (pinfunction "1_1") (pintype "passive"))
    )
    (net (code "65") (name "unconnected-(R9-Pad2)") (class "Default")
      (node (ref "R9") (pin "2") (pinfunction "2_2") (pintype "passive"))
    )
    (net (code "66") (name "unconnected-(R10-Pad1)") (class "Default")
      (node (ref "R10") (pin "1") (pinfunction "1_1") (pintype "passive"))
    )
    (net (code "67") (name "unconnected-(R10-Pad2)") (class "Default")
      (node (ref "R10") (pin "2") (pinfunction "2_2") (pintype "passive"))
    )
    (net (code "68") (name "unconnected-(R11-Pad1)") (class "Default")
      (node (ref "R11") (pin "1") (pinfunction "1_1") (pintype "passive"))
    )
    (net (code "69") (name "unconnected-(R11-Pad2)") (class "Default")
      (node (ref "R11") (pin "2") (pinfunction "2_2") (pintype "passive"))
    )
    (net (code "70") (name "unconnected-(R12-Pad1)") (class "Default")
      (node (ref "R12") (pin "1") (pinfunction "1_1") (pintype "passive"))
    )
    (net (code "71") (name "unconnected-(R12-Pad2)") (class "Default")
      (node (ref "R12") (pin "2") (pinfunction "2_2") (pintype "passive"))
    )
    (net (code "72") (name "unconnected-(R13-Pad1)") (class "Default")
      (node (ref "R13") (pin "1") (pinfunction "1_1") (pintype "passive"))
    )
    (net (code "73") (name "unconnected-(R13-Pad2)") (class "Default")
      (node (ref "R13") (pin "2") (pinfunction "2_2") (pintype "passive"))
    )
    (net (code "74") (name "unconnected-(R14-Pad1)") (class "Default")
      (node (ref "R14") (pin "1") (pinfunction "1_1") (pintype "passive"))
    )
    (net (code "75") (name "unconnected-(R14-Pad2)") (class "Default")
      (node (ref "R14") (pin "2") (pinfunction "2_2") (pintype "passive"))
    )
    (net (code "76") (name "unconnected-(R15-Pad1)") (class "Default")
      (node (ref "R15") (pin "1") (pinfunction "1_1") (pintype "passive"))
    )
    (net (code "77") (name "unconnected-(R15-Pad2)") (class "Default")
      (node (ref "R15") (pin "2") (pinfunction "2_2") (pintype "passive"))
    )
    (net (code "78") (name "unconnected-(S1-Pad1)") (class "Default")
      (node (ref "S1") (pin "1") (pinfunction "1_1") (pintype "passive"))
    )
    (net (code "79") (name "unconnected-(S1-Pad4)") (class "Default")
      (node (ref "S1") (pin "4") (pinfunction "4_4") (pintype "passive"))
    )
    (net (code "80") (name "unconnected-(S2-Pad1)") (class "Default")
      (node (ref "S2") (pin "1") (pinfunction "1_1") (pintype "passive"))
    )
    (net (code "81") (name "unconnected-(S2-Pad4)") (class "Default")
      (node (ref "S2") (pin "4") (pinfunction "4_4") (pintype "passive"))
    )
    (net (code "82") (name "unconnected-(S3-Pad1)") (class "Default")
      (node (ref "S3") (pin "1") (pinfunction "1_1") (pintype "passive"))
    )
    (net (code "83") (name "unconnected-(S3-Pad4)") (class "Default")
      (node (ref "S3") (pin "4") (pinfunction "4_4") (pintype "passive"))
    )
    (net (code "84") (name "unconnected-(S4-Pad1)") (class "Default")
      (node (ref "S4") (pin "1") (pinfunction "1_1") (pintype "passive"))
    )
    (net (code "85") (name "unconnected-(S4-Pad4)") (class "Default")
      (node (ref "S4") (pin "4") (pinfunction "4_4") (pintype "passive"))
    )
    (net (code "86") (name "unconnected-(U1-CSB-Pad2)") (class "Default")
      (node (ref "U1") (pin "2") (pinfunction "CSB_2") (pintype "input"))
    )
    (net (code "87") (name "unconnected-(U1-SDO-Pad5)") (class "Default")
      (node (ref "U1") (pin "5") (pinfunction "SDO_5") (pintype "bidirectional"))
    )
    (net (code "88") (name "unconnected-(U2-GND_2-Pad15)") (class "Default")
      (node (ref "U2") (pin "15") (pinfunction "GND_2_15") (pintype "bidirectional"))
    )
    (net (code "89") (name "unconnected-(U2-P0.4-Pad41)") (class "Default")
      (node (ref "U2") (pin "41") (pinfunction "P0.4_41") (pintype "bidirectional"))
    )
    (net (code "90") (name "unconnected-(U2-P0.5-Pad2)") (class "Default")
      (node (ref "U2") (pin "2") (pinfunction "P0.5_2") (pintype "bidirectional"))
    )
    (net (code "91") (name "unconnected-(U2-P5.2-Pad38)") (class "Default")
      (node (ref "U2") (pin "38") (pinfunction "P5.2_38") (pintype "bidirectional"))
    )
    (net (code "92") (name "unconnected-(U2-P5.3-Pad37)") (class "Default")
      (node (ref "U2") (pin "37") (pinfunction "P5.3_37") (pintype "bidirectional"))
    )
    (net (code "93") (name "unconnected-(U2-P5.5-Pad36)") (class "Default")
      (node (ref "U2") (pin "36") (pinfunction "P5.5_36") (pintype "bidirectional"))
    )
    (net (code "94") (name "unconnected-(U2-P5.6-Pad32)") (class "Default")
      (node (ref "U2") (pin "32") (pinfunction "P5.6_32") (pintype "bidirectional"))
    )
    (net (code "95") (name "unconnected-(U2-P6.2-Pad28)") (class "Default")
      (node (ref "U2") (pin "28") (pinfunction "P6.2_28") (pintype "bidirectional"))
    )
    (net (code "96") (name "unconnected-(U2-P6.3-Pad30)") (class "Default")
      (node (ref "U2") (pin "30") (pinfunction "P6.3_30") (pintype "bidirectional"))
    )
    (net (code "97") (name "unconnected-(U2-P6.5-Pad29)") (class "Default")
      (node (ref "U2") (pin "29") (pinfunction "P6.5_29") (pintype "bidirectional"))
    )
    (net (code "98") (name "unconnected-(U2-P7.1-Pad23)") (class "Default")
      (node (ref "U2") (pin "23") (pinfunction "P7.1_23") (pintype "bidirectional"))
    )
    (net (code "99") (name "unconnected-(U2-P7.2-Pad22)") (class "Default")
      (node (ref "U2") (pin "22") (pinfunction "P7.2_22") (pintype "bidirectional"))
    )
    (net (code "100") (name "unconnected-(U2-P7.7-Pad31)") (class "Default")
      (node (ref "U2") (pin "31") (pinfunction "P7.7_31") (pintype "bidirectional"))
    )
    (net (code "101") (name "unconnected-(U2-P9.2-Pad21)") (class "Default")
      (node (ref "U2") (pin "21") (pinfunction "P9.2_21") (pintype "bidirectional"))
    )
    (net (code "102") (name "unconnected-(U2-P9.3-Pad9)") (class "Default")
      (node (ref "U2") (pin "9") (pinfunction "P9.3_9") (pintype "bidirectional"))
    )
    (net (code "103") (name "unconnected-(U2-P10.2-Pad33)") (class "Default")
      (node (ref "U2") (pin "33") (pinfunction "P10.2_33") (pintype "bidirectional"))
    )
    (net (code "104") (name "unconnected-(U2-P10.3-Pad7)") (class "Default")
      (node (ref "U2") (pin "7") (pinfunction "P10.3_7") (pintype "bidirectional"))
    )
    (net (code "105") (name "unconnected-(U2-P10.6-Pad10)") (class "Default")
      (node (ref "U2") (pin "10") (pinfunction "P10.6_10") (pintype "bidirectional"))
    )
    (net (code "106") (name "unconnected-(U2-P12.6-Pad34)") (class "Default")
      (node (ref "U2") (pin "34") (pinfunction "P12.6_34") (pintype "bidirectional"))
    )
    (net (code "107") (name "unconnected-(U2-P12.7-Pad35)") (class "Default")
      (node (ref "U2") (pin "35") (pinfunction "P12.7_35") (pintype "bidirectional"))
    )
  )
)
